# smartBattery.net
KiCad netlist of a schematic drawn in Altium Designer
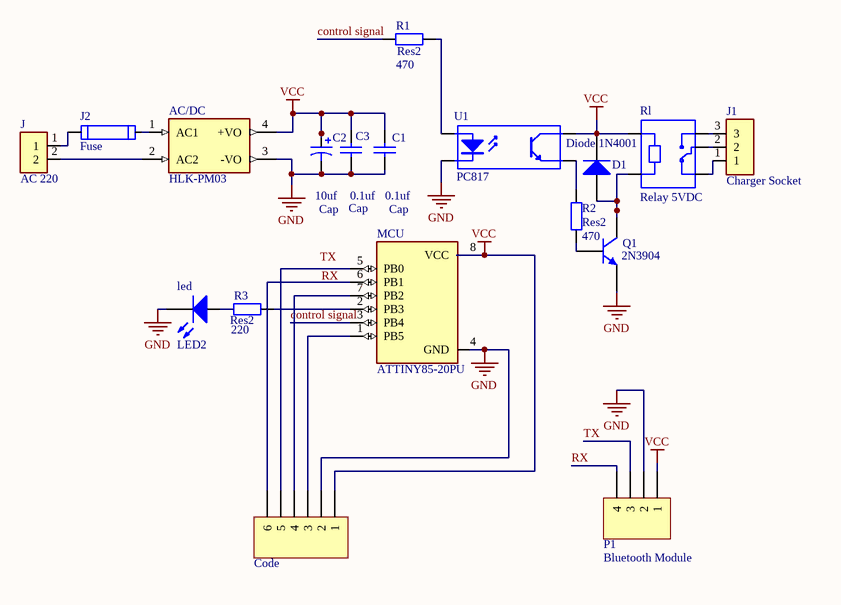
[diagram p0: smartBattery.SchDoc]

(export (version "E")
  (design (tool "Eeschema 10.0.6"))
  (components
    (comp (ref "AC/DC")
      (value "HLK-PM03")
      (footprint "CONV_HLK-PM03")
      (description "AC DC 3W power module")
      (fields (field (name "MF") "Hi-link"))
      (libsource (lib "HLK-PM03") (part "HLK-PM03"))
    )
    (comp (ref "C1")
      (value "Cap")
      (footprint "RAD-0.3")
      (description "Capacitor")
      (fields (field (name "ALTIUM_VALUE") "0.1uf") (field (name "PUBLISHER") "Altium Limited"))
      (libsource (lib "Miscellaneous Devices") (part "Cap"))
    )
    (comp (ref "C2")
      (value "Cap")
      (footprint "RB7.6-15")
      (description "Polarized Capacitor (Radial)")
      (fields (field (name "ALTIUM_VALUE") "10uf") (field (name "PUBLISHER") "Altium Limited"))
      (libsource (lib "Miscellaneous Devices") (part "Cap Pol1"))
    )
    (comp (ref "C3")
      (value "Cap")
      (footprint "RAD-0.3")
      (description "Capacitor")
      (fields (field (name "ALTIUM_VALUE") "0.1uf") (field (name "PUBLISHER") "Altium Limited"))
      (libsource (lib "Miscellaneous Devices") (part "Cap"))
    )
    (comp (ref "Code")
      (value "~")
      (footprint "HDR1X6")
      (description "Header, 6-Pin")
      (fields (field (name "PUBLISHER") "Altium Limited"))
      (libsource (lib "Miscellaneous Connectors") (part "Header 6"))
    )
    (comp (ref "D1")
      (value "Diode 1N4001")
      (footprint "DO-41")
      (description "1 Amp General Purpose Rectifier")
      (fields (field (name "PUBLISHER") "Altium Limited"))
      (libsource (lib "Miscellaneous Devices") (part "Diode 1N4001"))
    )
    (comp (ref "J")
      (value "AC 220")
      (footprint "CONN_282834-2")
      (description "Wire-To-Board Terminal Block, 2, 150 V, 10 A, 30 Awg, 16 Awg, 1.4 Mm")
      (fields (field (name "MF") "TE Connectivity") (field (name "MP") "282834-2"))
      (libsource (lib "282834-2") (part "282834-2"))
    )
    (comp (ref "J1")
      (value "Charger Socket")
      (footprint "TE_282834-3")
      (description "3 Position Wire to Board Terminal Block Horizontal with Board 0.100 (2.54mm)")
      (fields (field (name "MF") "TE Connectivity") (field (name "MP") "282834-3"))
      (libsource (lib "282834-3") (part "282834-3"))
    )
    (comp (ref "J2")
      (value "Fuse")
      (footprint "696310001002")
      (description "Fuse Holder 20A 250V 1 Circuit Cartridge Through Hole")
      (fields (field (name "MP") "696310001002") (field (name "MF") "Wurth Electronics"))
      (libsource (lib "696310001002") (part "696310001002"))
    )
    (comp (ref "led")
      (value "LED2")
      (footprint "3.2X1.6X1.1")
      (description "Typical RED, GREEN, YELLOW, AMBER GaAs LED")
      (fields (field (name "PUBLISHER") "Altium Limited"))
      (libsource (lib "Miscellaneous Devices") (part "LED2"))
    )
    (comp (ref "MCU")
      (value "ATTINY85-20PU")
      (footprint "DIP762W46P254L927H533Q8B")
      (fields (field (name "MF") "Microchip"))
      (libsource (lib "ATTINY85-20PU") (part "ATTINY85-20PU"))
    )
    (comp (ref "P1")
      (value "Bluetooth Module")
      (footprint "HDR1X4")
      (description "Header, 4-Pin")
      (fields (field (name "PUBLISHER") "Altium Limited"))
      (libsource (lib "Miscellaneous Connectors") (part "Header 4"))
    )
    (comp (ref "Q1")
      (value "2N3904")
      (footprint "TO-92A")
      (description "NPN General Purpose Amplifier")
      (fields (field (name "PUBLISHER") "Altium Limited"))
      (libsource (lib "Miscellaneous Devices") (part "2N3904"))
    )
    (comp (ref "R1")
      (value "Res2")
      (footprint "AXIAL-0.4")
      (description "Resistor")
      (fields (field (name "ALTIUM_VALUE") "470") (field (name "PUBLISHER") "Altium Limited"))
      (libsource (lib "") (part "Res2_1"))
    )
    (comp (ref "R2")
      (value "Res2")
      (footprint "AXIAL-0.4")
      (description "Resistor")
      (fields (field (name "ALTIUM_VALUE") "470") (field (name "PUBLISHER") "Altium Limited"))
      (libsource (lib "Miscellaneous Devices") (part "Res2"))
    )
    (comp (ref "R3")
      (value "Res2")
      (footprint "AXIAL-0.4")
      (description "Resistor")
      (fields (field (name "ALTIUM_VALUE") "220") (field (name "PUBLISHER") "Altium Limited"))
      (libsource (lib "") (part "Res2_1"))
    )
    (comp (ref "Rl")
      (value "Relay 5VDC")
      (footprint "RELAY_SRD-05VDC-SL-C")
      (fields (field (name "MP") "SRD-05VDC-SL-C") (field (name "MF") "Songle Relay"))
      (libsource (lib "SRD-05VDC-SL-C") (part "SRD-05VDC-SL-C"))
    )
    (comp (ref "U1")
      (value "PC817")
      (footprint "DIP-4")
      (description "4-Pin Phototransistor Optocoupler")
      (fields (field (name "PUBLISHER") "Altium Limited"))
      (libsource (lib "Miscellaneous Devices") (part "Optoisolator1"))
    )
  )
  (nets
    (net (code "1") (name "/RX") (class "Default")
      (node (ref "P1") (pin "4") (pinfunction "4_4") (pintype "passive"))
    )
    (net (code "2") (name "/TX") (class "Default")
      (node (ref "P1") (pin "3") (pinfunction "3_3") (pintype "passive"))
    )
    (net (code "3") (name "/control signal") (class "Default")
      (node (ref "MCU") (pin "3") (pinfunction "PB4_3") (pintype "bidirectional"))
      (node (ref "R1") (pin "1") (pinfunction "1_1") (pintype "passive"))
    )
    (net (code "4") (name "GND") (class "Default")
      (node (ref "AC/DC") (pin "3") (pinfunction "-VO_3") (pintype "output"))
      (node (ref "C1") (pin "1") (pinfunction "1_1") (pintype "passive"))
      (node (ref "C2") (pin "2") (pinfunction "2_2") (pintype "passive"))
      (node (ref "C3") (pin "1") (pinfunction "1_1") (pintype "passive"))
      (node (ref "Code") (pin "2") (pinfunction "2_2") (pintype "passive"))
      (node (ref "MCU") (pin "4") (pinfunction "GND_4") (pintype "power_in"))
      (node (ref "P1") (pin "2") (pinfunction "2_2") (pintype "passive"))
      (node (ref "Q1") (pin "1") (pinfunction "E_1") (pintype "passive"))
      (node (ref "U1") (pin "2") (pinfunction "K_2") (pintype "passive"))
      (node (ref "led") (pin "2") (pinfunction "K_2") (pintype "passive"))
    )
    (net (code "5") (name "Net-(AC/DC-AC1)") (class "Default")
      (node (ref "AC/DC") (pin "1") (pinfunction "AC1_1") (pintype "input"))
      (node (ref "J2") (pin "2") (pinfunction "2_2") (pintype "passive"))
    )
    (net (code "6") (name "Net-(AC/DC-AC2)") (class "Default")
      (node (ref "AC/DC") (pin "2") (pinfunction "AC2_2") (pintype "input"))
      (node (ref "J") (pin "2") (pinfunction "2_2") (pintype "passive"))
    )
    (net (code "7") (name "Net-(D1-A)") (class "Default")
      (node (ref "D1") (pin "1") (pinfunction "A_1") (pintype "passive"))
      (node (ref "Q1") (pin "3") (pinfunction "C_3") (pintype "passive"))
      (node (ref "Rl") (pin "A2") (pinfunction "A2_A2") (pintype "passive"))
    )
    (net (code "8") (name "Net-(J-Pad1)") (class "Default")
      (node (ref "J") (pin "1") (pinfunction "1_1") (pintype "passive"))
      (node (ref "J2") (pin "1") (pinfunction "1_1") (pintype "passive"))
    )
    (net (code "9") (name "Net-(J1-Pad1)") (class "Default")
      (node (ref "J1") (pin "1") (pinfunction "1_1") (pintype "passive"))
      (node (ref "Rl") (pin "NC") (pinfunction "NC_NC") (pintype "passive"))
    )
    (net (code "10") (name "Net-(J1-Pad2)") (class "Default")
      (node (ref "J1") (pin "2") (pinfunction "2_2") (pintype "passive"))
      (node (ref "Rl") (pin "COM") (pinfunction "COM_COM") (pintype "passive"))
    )
    (net (code "11") (name "Net-(J1-Pad3)") (class "Default")
      (node (ref "J1") (pin "3") (pinfunction "3_3") (pintype "passive"))
      (node (ref "Rl") (pin "NO") (pinfunction "NO_NO") (pintype "passive"))
    )
    (net (code "12") (name "Net-(MCU-PB0)") (class "Default")
      (node (ref "Code") (pin "5") (pinfunction "5_5") (pintype "passive"))
      (node (ref "MCU") (pin "5") (pinfunction "PB0_5") (pintype "bidirectional"))
    )
    (net (code "13") (name "Net-(MCU-PB1)") (class "Default")
      (node (ref "Code") (pin "6") (pinfunction "6_6") (pintype "passive"))
      (node (ref "MCU") (pin "6") (pinfunction "PB1_6") (pintype "bidirectional"))
    )
    (net (code "14") (name "Net-(MCU-PB2)") (class "Default")
      (node (ref "Code") (pin "4") (pinfunction "4_4") (pintype "passive"))
      (node (ref "MCU") (pin "7") (pinfunction "PB2_7") (pintype "bidirectional"))
    )
    (net (code "15") (name "Net-(MCU-PB3)") (class "Default")
      (node (ref "MCU") (pin "2") (pinfunction "PB3_2") (pintype "bidirectional"))
      (node (ref "R3") (pin "2") (pinfunction "2_2") (pintype "passive"))
    )
    (net (code "16") (name "Net-(MCU-PB5)") (class "Default")
      (node (ref "Code") (pin "3") (pinfunction "3_3") (pintype "passive"))
      (node (ref "MCU") (pin "1") (pinfunction "PB5_1") (pintype "bidirectional"))
    )
    (net (code "17") (name "Net-(Q1-B)") (class "Default")
      (node (ref "Q1") (pin "2") (pinfunction "B_2") (pintype "passive"))
      (node (ref "R2") (pin "1") (pinfunction "1_1") (pintype "passive"))
    )
    (net (code "18") (name "Net-(U1-A)") (class "Default")
      (node (ref "R1") (pin "2") (pinfunction "2_2") (pintype "passive"))
      (node (ref "U1") (pin "1") (pinfunction "A_1") (pintype "passive"))
    )
    (net (code "19") (name "Net-(U1-E)") (class "Default")
      (node (ref "R2") (pin "2") (pinfunction "2_2") (pintype "passive"))
      (node (ref "U1") (pin "3") (pinfunction "E_3") (pintype "passive"))
    )
    (net (code "20") (name "Net-(led-A)") (class "Default")
      (node (ref "R3") (pin "1") (pinfunction "1_1") (pintype "passive"))
      (node (ref "led") (pin "1") (pinfunction "A_1") (pintype "passive"))
    )
    (net (code "21") (name "VCC") (class "Default")
      (node (ref "AC/DC") (pin "4") (pinfunction "+VO_4") (pintype "output"))
      (node (ref "C1") (pin "2") (pinfunction "2_2") (pintype "passive"))
      (node (ref "C2") (pin "1") (pinfunction "1_1") (pintype "passive"))
      (node (ref "C3") (pin "2") (pinfunction "2_2") (pintype "passive"))
      (node (ref "Code") (pin "1") (pinfunction "1_1") (pintype "passive"))
      (node (ref "D1") (pin "2") (pinfunction "K_2") (pintype "passive"))
      (node (ref "MCU") (pin "8") (pinfunction "VCC_8") (pintype "power_in"))
      (node (ref "P1") (pin "1") (pinfunction "1_1") (pintype "passive"))
      (node (ref "Rl") (pin "A1") (pinfunction "A1_A1") (pintype "passive"))
      (node (ref "U1") (pin "4") (pinfunction "C_4") (pintype "passive"))
    )
  )
)
